# brobotESP12_2.net
KiCad netlist of a schematic drawn in EAGLE
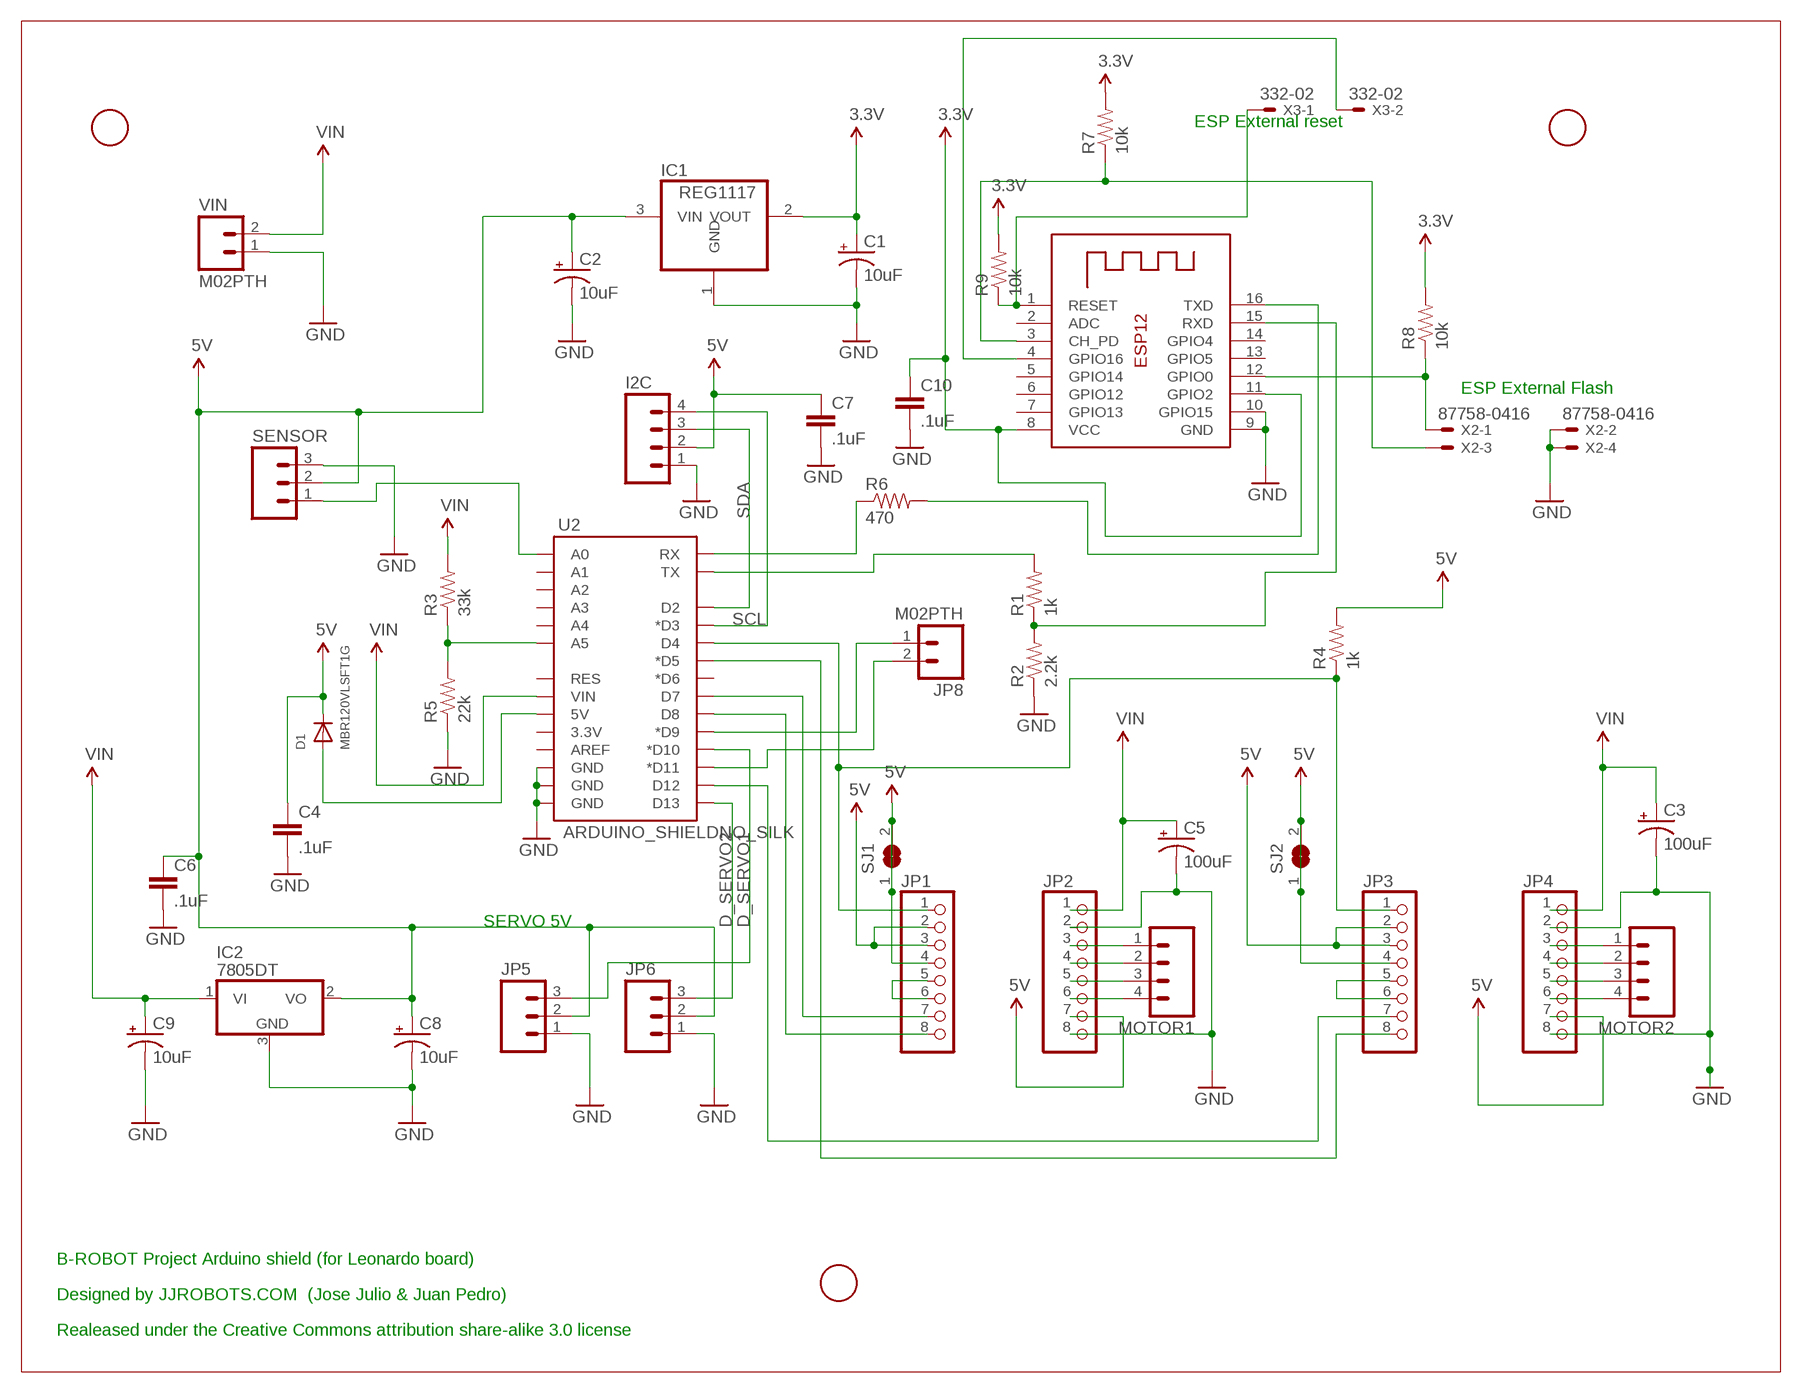
[diagram p0: schematic, sheet 1]
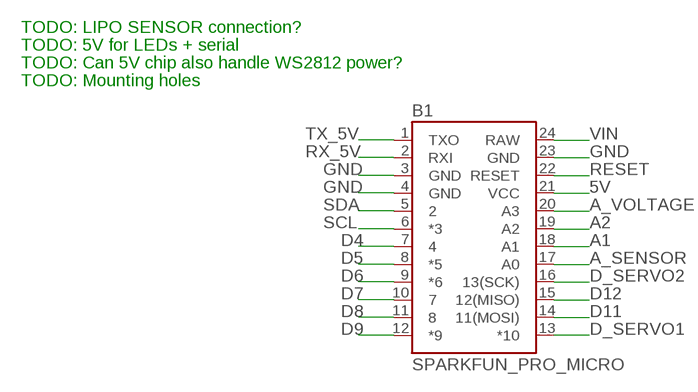
[diagram p1: schematic, sheet 2]

(export (version "E")
  (design (tool "Eeschema 10.0.6"))
  (components
    (comp (ref "B1")
      (value "SPARKFUN_PRO_MICRO")
      (footprint "eagle-import:SPARKFUN_PRO_MICRO")
      (libsource (lib "eagle-import") (part "SPARKFUN_PRO_MICRO"))
    )
    (comp (ref "C1")
      (value "10uF")
      (footprint "eagle-import:EIA3216")
      (libsource (lib "eagle-import") (part "CAP_POL1206"))
    )
    (comp (ref "C2")
      (value "10uF")
      (footprint "eagle-import:EIA3216")
      (libsource (lib "eagle-import") (part "CAP_POL1206"))
    )
    (comp (ref "C3")
      (value "100uF")
      (footprint "eagle-import:PANASONIC_D")
      (libsource (lib "eagle-import") (part "CAP_POLD"))
    )
    (comp (ref "C4")
      (value ".1uF")
      (footprint "eagle-import:0402-CAP")
      (libsource (lib "eagle-import") (part "CAP0402-CAP"))
    )
    (comp (ref "C5")
      (value "100uF")
      (footprint "eagle-import:PANASONIC_D")
      (libsource (lib "eagle-import") (part "CAP_POLD"))
    )
    (comp (ref "C6")
      (value ".1uF")
      (footprint "eagle-import:0402-CAP")
      (libsource (lib "eagle-import") (part "CAP0402-CAP"))
    )
    (comp (ref "C7")
      (value ".1uF")
      (footprint "eagle-import:0402-CAP")
      (libsource (lib "eagle-import") (part "CAP0402-CAP"))
    )
    (comp (ref "C8")
      (value "10uF")
      (footprint "eagle-import:EIA3216")
      (libsource (lib "eagle-import") (part "CAP_POL1206"))
    )
    (comp (ref "C9")
      (value "10uF")
      (footprint "eagle-import:EIA3216")
      (libsource (lib "eagle-import") (part "CAP_POL1206"))
    )
    (comp (ref "C10")
      (value ".1uF")
      (footprint "eagle-import:0402-CAP")
      (libsource (lib "eagle-import") (part "CAP0402-CAP"))
    )
    (comp (ref "D1")
      (value "MBR120VLSFT1G")
      (footprint "eagle-import:SOD-123")
      (libsource (lib "eagle-import") (part "DIODESOD-123"))
    )
    (comp (ref "I2C")
      (value "M04PTH")
      (footprint "eagle-import:1X04")
      (libsource (lib "eagle-import") (part "M04PTH"))
    )
    (comp (ref "IC1")
      (value "REG1117")
      (footprint "eagle-import:SOT223")
      (libsource (lib "eagle-import") (part "REG1117"))
    )
    (comp (ref "IC2")
      (value "7805DT")
      (footprint "eagle-import:TO252")
      (libsource (lib "eagle-import") (part "78DT05"))
    )
    (comp (ref "JP1")
      (value "PINHD-1X8")
      (footprint "eagle-import:1X08")
      (libsource (lib "eagle-import") (part "PINHD-1X8"))
    )
    (comp (ref "JP2")
      (value "PINHD-1X8")
      (footprint "eagle-import:1X08")
      (libsource (lib "eagle-import") (part "PINHD-1X8"))
    )
    (comp (ref "JP3")
      (value "PINHD-1X8")
      (footprint "eagle-import:1X08")
      (libsource (lib "eagle-import") (part "PINHD-1X8"))
    )
    (comp (ref "JP4")
      (value "PINHD-1X8")
      (footprint "eagle-import:1X08")
      (libsource (lib "eagle-import") (part "PINHD-1X8"))
    )
    (comp (ref "JP5")
      (value "M03PTH")
      (footprint "eagle-import:1X03")
      (libsource (lib "eagle-import") (part "M03PTH"))
    )
    (comp (ref "JP6")
      (value "M03PTH")
      (footprint "eagle-import:1X03")
      (libsource (lib "eagle-import") (part "M03PTH"))
    )
    (comp (ref "JP8")
      (value "M02PTH")
      (footprint "eagle-import:1X02")
      (libsource (lib "eagle-import") (part "M02PTH"))
    )
    (comp (ref "MOTOR1")
      (value "M04PTH")
      (footprint "eagle-import:1X04")
      (libsource (lib "eagle-import") (part "M04PTH"))
    )
    (comp (ref "MOTOR2")
      (value "M04PTH")
      (footprint "eagle-import:1X04")
      (libsource (lib "eagle-import") (part "M04PTH"))
    )
    (comp (ref "R1")
      (value "1k")
      (footprint "eagle-import:0805")
      (libsource (lib "eagle-import") (part "RESISTOR0805-RES"))
    )
    (comp (ref "R2")
      (value "2.2k")
      (footprint "eagle-import:0805")
      (libsource (lib "eagle-import") (part "RESISTOR0805-RES"))
    )
    (comp (ref "R3")
      (value "33k")
      (footprint "eagle-import:0805")
      (libsource (lib "eagle-import") (part "RESISTOR0805-RES"))
    )
    (comp (ref "R4")
      (value "1k")
      (footprint "eagle-import:0805")
      (libsource (lib "eagle-import") (part "RESISTOR0805-RES"))
    )
    (comp (ref "R5")
      (value "22k")
      (footprint "eagle-import:0805")
      (libsource (lib "eagle-import") (part "RESISTOR0805-RES"))
    )
    (comp (ref "R6")
      (value "470")
      (footprint "eagle-import:0805")
      (libsource (lib "eagle-import") (part "RESISTOR0805-RES"))
    )
    (comp (ref "R7")
      (value "10k")
      (footprint "eagle-import:0805")
      (libsource (lib "eagle-import") (part "RESISTOR0805-RES"))
    )
    (comp (ref "R8")
      (value "10k")
      (footprint "eagle-import:0805")
      (libsource (lib "eagle-import") (part "RESISTOR0805-RES"))
    )
    (comp (ref "R9")
      (value "10k")
      (footprint "eagle-import:0805")
      (libsource (lib "eagle-import") (part "RESISTOR0805-RES"))
    )
    (comp (ref "SENSOR")
      (value "M03PTH")
      (footprint "eagle-import:1X03")
      (libsource (lib "eagle-import") (part "M03PTH"))
    )
    (comp (ref "SJ1")
      (value "SJW")
      (footprint "eagle-import:SJW")
      (libsource (lib "eagle-import") (part "SJW"))
    )
    (comp (ref "SJ2")
      (value "SJW")
      (footprint "eagle-import:SJW")
      (libsource (lib "eagle-import") (part "SJW"))
    )
    (comp (ref "U$1")
      (value "FIDUCIAL")
      (footprint "eagle-import:FIDUCIAL_1MM")
      (libsource (lib "eagle-import") (part "FIDUCIAL"))
    )
    (comp (ref "U$2")
      (value "FIDUCIAL")
      (footprint "eagle-import:FIDUCIAL_1MM")
      (libsource (lib "eagle-import") (part "FIDUCIAL"))
    )
    (comp (ref "U$3")
      (value "FIDUCIAL")
      (footprint "eagle-import:FIDUCIAL_1MM")
      (libsource (lib "eagle-import") (part "FIDUCIAL"))
    )
    (comp (ref "U2")
      (value "ARDUINO_SHIELDNO_SILK")
      (footprint "eagle-import:DUEMILANOVE_VIAS")
      (libsource (lib "eagle-import") (part "ARDUINO_SHIELDNO_SILK"))
    )
    (comp (ref "VIN")
      (value "M02PTH")
      (footprint "eagle-import:1X02")
      (libsource (lib "eagle-import") (part "M02PTH"))
    )
    (comp (ref "X1")
      (value "ESP-12")
      (footprint "eagle-import:ESP-12")
      (libsource (lib "eagle-import") (part "ESP-12"))
    )
    (comp (ref "X2")
      (value "87758-0416")
      (footprint "eagle-import:87758-0416")
      (fields (field (name "MF") "FARNELL"))
      (libsource (lib "eagle-import") (part "87758-0416"))
    )
    (comp (ref "X3")
      (value "332-02")
      (footprint "eagle-import:332-02")
      (libsource (lib "eagle-import") (part "332-02"))
    )
  )
  (nets
    (net (code "1") (name "3.3V") (class "Default")
      (node (ref "C1") (pin "A") (pinfunction "+_A") (pintype "passive"))
      (node (ref "C10") (pin "1") (pinfunction "1_1") (pintype "passive"))
      (node (ref "IC1") (pin "2") (pinfunction "VOUT_2") (pintype "output"))
      (node (ref "R7") (pin "2") (pinfunction "2_2") (pintype "passive"))
      (node (ref "R8") (pin "2") (pinfunction "2_2") (pintype "passive"))
      (node (ref "R9") (pin "2") (pinfunction "2_2") (pintype "passive"))
      (node (ref "X1") (pin "11") (pinfunction "GPIO2_11") (pintype "bidirectional"))
      (node (ref "X1") (pin "8") (pinfunction "VCC_8") (pintype "power_in"))
    )
    (net (code "2") (name "5V") (class "Default")
      (node (ref "B1") (pin "21") (pinfunction "VCC_21") (pintype "power_in"))
      (node (ref "C2") (pin "A") (pinfunction "+_A") (pintype "passive"))
      (node (ref "C4") (pin "1") (pinfunction "1_1") (pintype "passive"))
      (node (ref "C6") (pin "1") (pinfunction "1_1") (pintype "passive"))
      (node (ref "C7") (pin "1") (pinfunction "1_1") (pintype "passive"))
      (node (ref "C8") (pin "A") (pinfunction "+_A") (pintype "passive"))
      (node (ref "D1") (pin "C") (pinfunction "C_C") (pintype "passive"))
      (node (ref "I2C") (pin "2") (pinfunction "2_2") (pintype "passive"))
      (node (ref "IC1") (pin "3") (pinfunction "VIN_3") (pintype "input"))
      (node (ref "IC2") (pin "2") (pinfunction "VO_2") (pintype "passive"))
      (node (ref "JP1") (pin "2") (pinfunction "2_2") (pintype "passive"))
      (node (ref "JP1") (pin "3") (pinfunction "3_3") (pintype "passive"))
      (node (ref "JP1") (pin "4") (pinfunction "4_4") (pintype "passive"))
      (node (ref "JP2") (pin "7") (pinfunction "7_7") (pintype "passive"))
      (node (ref "JP3") (pin "2") (pinfunction "2_2") (pintype "passive"))
      (node (ref "JP3") (pin "3") (pinfunction "3_3") (pintype "passive"))
      (node (ref "JP3") (pin "4") (pinfunction "4_4") (pintype "passive"))
      (node (ref "JP4") (pin "7") (pinfunction "7_7") (pintype "passive"))
      (node (ref "JP5") (pin "2") (pinfunction "2_2") (pintype "passive"))
      (node (ref "JP6") (pin "2") (pinfunction "2_2") (pintype "passive"))
      (node (ref "R4") (pin "2") (pinfunction "2_2") (pintype "passive"))
      (node (ref "SENSOR") (pin "2") (pinfunction "2_2") (pintype "passive"))
      (node (ref "SJ1") (pin "1") (pinfunction "1_1") (pintype "passive"))
      (node (ref "SJ1") (pin "2") (pinfunction "2_2") (pintype "passive"))
      (node (ref "SJ2") (pin "1") (pinfunction "1_1") (pintype "passive"))
      (node (ref "SJ2") (pin "2") (pinfunction "2_2") (pintype "passive"))
    )
    (net (code "3") (name "A1") (class "Default")
      (node (ref "B1") (pin "18") (pinfunction "A1_18") (pintype "bidirectional"))
    )
    (net (code "4") (name "A2") (class "Default")
      (node (ref "B1") (pin "19") (pinfunction "A2_19") (pintype "bidirectional"))
    )
    (net (code "5") (name "A_SENSOR") (class "Default")
      (node (ref "B1") (pin "17") (pinfunction "A0_17") (pintype "bidirectional"))
      (node (ref "SENSOR") (pin "1") (pinfunction "1_1") (pintype "passive"))
      (node (ref "U2") (pin "A0") (pinfunction "A0_A0") (pintype "bidirectional"))
    )
    (net (code "6") (name "A_VOLTAGE") (class "Default")
      (node (ref "B1") (pin "20") (pinfunction "A3_20") (pintype "bidirectional"))
      (node (ref "R3") (pin "1") (pinfunction "1_1") (pintype "passive"))
      (node (ref "R5") (pin "2") (pinfunction "2_2") (pintype "passive"))
      (node (ref "U2") (pin "A5") (pinfunction "A5_A5") (pintype "bidirectional"))
    )
    (net (code "7") (name "D4") (class "Default")
      (node (ref "B1") (pin "7") (pinfunction "4_7") (pintype "bidirectional"))
      (node (ref "JP1") (pin "1") (pinfunction "1_1") (pintype "passive"))
      (node (ref "JP3") (pin "1") (pinfunction "1_1") (pintype "passive"))
      (node (ref "R4") (pin "1") (pinfunction "1_1") (pintype "passive"))
      (node (ref "U2") (pin "D4") (pinfunction "D4_D4") (pintype "bidirectional"))
    )
    (net (code "8") (name "D5") (class "Default")
      (node (ref "B1") (pin "8") (pinfunction "*5_8") (pintype "bidirectional"))
      (node (ref "JP3") (pin "8") (pinfunction "8_8") (pintype "passive"))
      (node (ref "U2") (pin "D5") (pinfunction "*D5_D5") (pintype "bidirectional"))
    )
    (net (code "9") (name "D6") (class "Default")
      (node (ref "B1") (pin "9") (pinfunction "*6_9") (pintype "bidirectional"))
    )
    (net (code "10") (name "D7") (class "Default")
      (node (ref "B1") (pin "10") (pinfunction "7_10") (pintype "bidirectional"))
      (node (ref "JP1") (pin "7") (pinfunction "7_7") (pintype "passive"))
      (node (ref "U2") (pin "D7") (pinfunction "D7_D7") (pintype "bidirectional"))
    )
    (net (code "11") (name "D8") (class "Default")
      (node (ref "B1") (pin "11") (pinfunction "8_11") (pintype "bidirectional"))
      (node (ref "JP1") (pin "8") (pinfunction "8_8") (pintype "passive"))
      (node (ref "U2") (pin "D8") (pinfunction "D8_D8") (pintype "bidirectional"))
    )
    (net (code "12") (name "D9") (class "Default")
      (node (ref "B1") (pin "12") (pinfunction "*9_12") (pintype "bidirectional"))
    )
    (net (code "13") (name "D11") (class "Default")
      (node (ref "B1") (pin "14") (pinfunction "11(MOSI)_14") (pintype "bidirectional"))
      (node (ref "JP8") (pin "2") (pinfunction "2_2") (pintype "passive"))
      (node (ref "U2") (pin "D11") (pinfunction "*D11_D11") (pintype "bidirectional"))
    )
    (net (code "14") (name "D12") (class "Default")
      (node (ref "B1") (pin "15") (pinfunction "12(MISO)_15") (pintype "bidirectional"))
      (node (ref "JP3") (pin "7") (pinfunction "7_7") (pintype "passive"))
      (node (ref "U2") (pin "D12") (pinfunction "D12_D12") (pintype "bidirectional"))
    )
    (net (code "15") (name "D_SERVO1") (class "Default")
      (node (ref "B1") (pin "13") (pinfunction "*10_13") (pintype "bidirectional"))
      (node (ref "JP5") (pin "3") (pinfunction "3_3") (pintype "passive"))
      (node (ref "U2") (pin "D10") (pinfunction "*D10_D10") (pintype "bidirectional"))
    )
    (net (code "16") (name "D_SERVO2") (class "Default")
      (node (ref "B1") (pin "16") (pinfunction "13(SCK)_16") (pintype "bidirectional"))
      (node (ref "JP6") (pin "3") (pinfunction "3_3") (pintype "passive"))
      (node (ref "U2") (pin "D13") (pinfunction "D13_D13") (pintype "bidirectional"))
    )
    (net (code "17") (name "GND") (class "Default")
      (node (ref "B1") (pin "23") (pinfunction "GND_23") (pintype "power_in"))
      (node (ref "B1") (pin "3") (pinfunction "GND_3") (pintype "power_in"))
      (node (ref "B1") (pin "4") (pinfunction "GND_4") (pintype "power_in"))
      (node (ref "C1") (pin "C") (pinfunction "-_C") (pintype "passive"))
      (node (ref "C10") (pin "2") (pinfunction "2_2") (pintype "passive"))
      (node (ref "C2") (pin "C") (pinfunction "-_C") (pintype "passive"))
      (node (ref "C3") (pin "-") (pinfunction "-_-") (pintype "passive"))
      (node (ref "C4") (pin "2") (pinfunction "2_2") (pintype "passive"))
      (node (ref "C5") (pin "-") (pinfunction "-_-") (pintype "passive"))
      (node (ref "C6") (pin "2") (pinfunction "2_2") (pintype "passive"))
      (node (ref "C7") (pin "2") (pinfunction "2_2") (pintype "passive"))
      (node (ref "C8") (pin "C") (pinfunction "-_C") (pintype "passive"))
      (node (ref "C9") (pin "C") (pinfunction "-_C") (pintype "passive"))
      (node (ref "I2C") (pin "1") (pinfunction "1_1") (pintype "passive"))
      (node (ref "IC1") (pin "1") (pinfunction "GND_1") (pintype "power_in"))
      (node (ref "IC2") (pin "3") (pinfunction "GND_3") (pintype "passive"))
      (node (ref "JP2") (pin "2") (pinfunction "2_2") (pintype "passive"))
      (node (ref "JP2") (pin "8") (pinfunction "8_8") (pintype "passive"))
      (node (ref "JP4") (pin "2") (pinfunction "2_2") (pintype "passive"))
      (node (ref "JP4") (pin "8") (pinfunction "8_8") (pintype "passive"))
      (node (ref "JP5") (pin "1") (pinfunction "1_1") (pintype "passive"))
      (node (ref "JP6") (pin "1") (pinfunction "1_1") (pintype "passive"))
      (node (ref "R2") (pin "1") (pinfunction "1_1") (pintype "passive"))
      (node (ref "R5") (pin "1") (pinfunction "1_1") (pintype "passive"))
      (node (ref "SENSOR") (pin "3") (pinfunction "3_3") (pintype "passive"))
      (node (ref "U2") (pin "GND@0") (pinfunction "GND_GND@0") (pintype "bidirectional"))
      (node (ref "U2") (pin "GND@1") (pinfunction "GND_GND@1") (pintype "bidirectional"))
      (node (ref "U2") (pin "GND@2") (pinfunction "GND_GND@2") (pintype "bidirectional"))
      (node (ref "VIN") (pin "1") (pinfunction "1_1") (pintype "passive"))
      (node (ref "X1") (pin "10") (pinfunction "GPIO15_10") (pintype "bidirectional"))
      (node (ref "X1") (pin "9") (pinfunction "GND_9") (pintype "power_in"))
      (node (ref "X2") (pin "2") (pinfunction "S_2") (pintype "passive"))
      (node (ref "X2") (pin "4") (pinfunction "S_4") (pintype "passive"))
    )
    (net (code "18") (name "Net-(D1-PadA)") (class "Default")
      (node (ref "D1") (pin "A") (pinfunction "A_A") (pintype "passive"))
      (node (ref "U2") (pin "5V") (pinfunction "5V_5V") (pintype "bidirectional"))
    )
    (net (code "19") (name "Net-(JP1-Pad5)") (class "Default")
      (node (ref "JP1") (pin "5") (pinfunction "5_5") (pintype "passive"))
      (node (ref "JP1") (pin "6") (pinfunction "6_6") (pintype "passive"))
    )
    (net (code "20") (name "Net-(JP2-Pad3)") (class "Default")
      (node (ref "JP2") (pin "3") (pinfunction "3_3") (pintype "passive"))
      (node (ref "MOTOR1") (pin "1") (pinfunction "1_1") (pintype "passive"))
    )
    (net (code "21") (name "Net-(JP2-Pad4)") (class "Default")
      (node (ref "JP2") (pin "4") (pinfunction "4_4") (pintype "passive"))
      (node (ref "MOTOR1") (pin "2") (pinfunction "2_2") (pintype "passive"))
    )
    (net (code "22") (name "Net-(JP2-Pad5)") (class "Default")
      (node (ref "JP2") (pin "5") (pinfunction "5_5") (pintype "passive"))
      (node (ref "MOTOR1") (pin "3") (pinfunction "3_3") (pintype "passive"))
    )
    (net (code "23") (name "Net-(JP2-Pad6)") (class "Default")
      (node (ref "JP2") (pin "6") (pinfunction "6_6") (pintype "passive"))
      (node (ref "MOTOR1") (pin "4") (pinfunction "4_4") (pintype "passive"))
    )
    (net (code "24") (name "Net-(JP3-Pad5)") (class "Default")
      (node (ref "JP3") (pin "5") (pinfunction "5_5") (pintype "passive"))
      (node (ref "JP3") (pin "6") (pinfunction "6_6") (pintype "passive"))
    )
    (net (code "25") (name "Net-(JP4-Pad3)") (class "Default")
      (node (ref "JP4") (pin "3") (pinfunction "3_3") (pintype "passive"))
      (node (ref "MOTOR2") (pin "1") (pinfunction "1_1") (pintype "passive"))
    )
    (net (code "26") (name "Net-(JP4-Pad4)") (class "Default")
      (node (ref "JP4") (pin "4") (pinfunction "4_4") (pintype "passive"))
      (node (ref "MOTOR2") (pin "2") (pinfunction "2_2") (pintype "passive"))
    )
    (net (code "27") (name "Net-(JP4-Pad5)") (class "Default")
      (node (ref "JP4") (pin "5") (pinfunction "5_5") (pintype "passive"))
      (node (ref "MOTOR2") (pin "3") (pinfunction "3_3") (pintype "passive"))
    )
    (net (code "28") (name "Net-(JP4-Pad6)") (class "Default")
      (node (ref "JP4") (pin "6") (pinfunction "6_6") (pintype "passive"))
      (node (ref "MOTOR2") (pin "4") (pinfunction "4_4") (pintype "passive"))
    )
    (net (code "29") (name "Net-(U2-*D9)") (class "Default")
      (node (ref "JP8") (pin "1") (pinfunction "1_1") (pintype "passive"))
      (node (ref "U2") (pin "D9") (pinfunction "*D9_D9") (pintype "bidirectional"))
    )
    (net (code "30") (name "Net-(X1-CH_PD)") (class "Default")
      (node (ref "R7") (pin "1") (pinfunction "1_1") (pintype "passive"))
      (node (ref "X1") (pin "3") (pinfunction "CH_PD_3") (pintype "input"))
      (node (ref "X2") (pin "3") (pinfunction "S_3") (pintype "passive"))
    )
    (net (code "31") (name "Net-(X1-GPIO0)") (class "Default")
      (node (ref "R8") (pin "1") (pinfunction "1_1") (pintype "passive"))
      (node (ref "X1") (pin "12") (pinfunction "GPIO0_12") (pintype "bidirectional"))
      (node (ref "X2") (pin "1") (pinfunction "S_1") (pintype "passive"))
    )
    (net (code "32") (name "Net-(X1-GPIO16)") (class "Default")
      (node (ref "X1") (pin "4") (pinfunction "GPIO16_4") (pintype "bidirectional"))
      (node (ref "X3") (pin "2") (pinfunction "S_2") (pintype "passive"))
    )
    (net (code "33") (name "Net-(X1-RESET)") (class "Default")
      (node (ref "R9") (pin "1") (pinfunction "1_1") (pintype "passive"))
      (node (ref "X1") (pin "1") (pinfunction "RESET_1") (pintype "input"))
      (node (ref "X3") (pin "1") (pinfunction "S_1") (pintype "passive"))
    )
    (net (code "34") (name "Net-(X1-RXD)") (class "Default")
      (node (ref "R1") (pin "1") (pinfunction "1_1") (pintype "passive"))
      (node (ref "R2") (pin "2") (pinfunction "2_2") (pintype "passive"))
      (node (ref "X1") (pin "15") (pinfunction "RXD_15") (pintype "input"))
    )
    (net (code "35") (name "Net-(X1-TXD)") (class "Default")
      (node (ref "R6") (pin "2") (pinfunction "2_2") (pintype "passive"))
      (node (ref "X1") (pin "16") (pinfunction "TXD_16") (pintype "output"))
    )
    (net (code "36") (name "RESET") (class "Default")
      (node (ref "B1") (pin "22") (pinfunction "RESET_22") (pintype "bidirectional"))
    )
    (net (code "37") (name "RX_5V") (class "Default")
      (node (ref "B1") (pin "2") (pinfunction "RXI_2") (pintype "bidirectional"))
      (node (ref "R6") (pin "1") (pinfunction "1_1") (pintype "passive"))
      (node (ref "U2") (pin "RX") (pinfunction "RX_RX") (pintype "bidirectional"))
    )
    (net (code "38") (name "SCL") (class "Default")
      (node (ref "B1") (pin "6") (pinfunction "*3_6") (pintype "bidirectional"))
      (node (ref "I2C") (pin "4") (pinfunction "4_4") (pintype "passive"))
      (node (ref "U2") (pin "D3") (pinfunction "*D3_D3") (pintype "bidirectional"))
    )
    (net (code "39") (name "SDA") (class "Default")
      (node (ref "B1") (pin "5") (pinfunction "2_5") (pintype "bidirectional"))
      (node (ref "I2C") (pin "3") (pinfunction "3_3") (pintype "passive"))
      (node (ref "U2") (pin "D2") (pinfunction "D2_D2") (pintype "bidirectional"))
    )
    (net (code "40") (name "TX_5V") (class "Default")
      (node (ref "B1") (pin "1") (pinfunction "TXO_1") (pintype "bidirectional"))
      (node (ref "R1") (pin "2") (pinfunction "2_2") (pintype "passive"))
      (node (ref "U2") (pin "TX") (pinfunction "TX_TX") (pintype "bidirectional"))
    )
    (net (code "41") (name "VIN") (class "Default")
      (node (ref "B1") (pin "24") (pinfunction "RAW_24") (pintype "power_in"))
      (node (ref "C3") (pin "+") (pinfunction "+_+") (pintype "passive"))
      (node (ref "C5") (pin "+") (pinfunction "+_+") (pintype "passive"))
      (node (ref "C9") (pin "A") (pinfunction "+_A") (pintype "passive"))
      (node (ref "IC2") (pin "1") (pinfunction "VI_1") (pintype "input"))
      (node (ref "JP2") (pin "1") (pinfunction "1_1") (pintype "passive"))
      (node (ref "JP4") (pin "1") (pinfunction "1_1") (pintype "passive"))
      (node (ref "R3") (pin "2") (pinfunction "2_2") (pintype "passive"))
      (node (ref "U2") (pin "VIN") (pinfunction "VIN_VIN") (pintype "bidirectional"))
      (node (ref "VIN") (pin "2") (pinfunction "2_2") (pintype "passive"))
    )
    (net (code "42") (name "unconnected-(U2-*D6-PadD6)") (class "Default")
      (node (ref "U2") (pin "D6") (pinfunction "*D6_D6") (pintype "bidirectional"))
    )
    (net (code "43") (name "unconnected-(U2-Pad3.3V)") (class "Default")
      (node (ref "U2") (pin "3.3V") (pinfunction "3.3V_3.3V") (pintype "bidirectional"))
    )
    (net (code "44") (name "unconnected-(U2-PadA1)") (class "Default")
      (node (ref "U2") (pin "A1") (pinfunction "A1_A1") (pintype "bidirectional"))
    )
    (net (code "45") (name "unconnected-(U2-PadA2)") (class "Default")
      (node (ref "U2") (pin "A2") (pinfunction "A2_A2") (pintype "bidirectional"))
    )
    (net (code "46") (name "unconnected-(U2-PadA3)") (class "Default")
      (node (ref "U2") (pin "A3") (pinfunction "A3_A3") (pintype "bidirectional"))
    )
    (net (code "47") (name "unconnected-(U2-PadA4)") (class "Default")
      (node (ref "U2") (pin "A4") (pinfunction "A4_A4") (pintype "bidirectional"))
    )
    (net (code "48") (name "unconnected-(U2-PadAREF)") (class "Default")
      (node (ref "U2") (pin "AREF") (pinfunction "AREF_AREF") (pintype "bidirectional"))
    )
    (net (code "49") (name "unconnected-(U2-PadRES)") (class "Default")
      (node (ref "U2") (pin "RES") (pinfunction "RES_RES") (pintype "bidirectional"))
    )
    (net (code "50") (name "unconnected-(X1-ADC-Pad2)") (class "Default")
      (node (ref "X1") (pin "2") (pinfunction "ADC_2") (pintype "passive"))
    )
    (net (code "51") (name "unconnected-(X1-GPIO4-Pad14)") (class "Default")
      (node (ref "X1") (pin "14") (pinfunction "GPIO4_14") (pintype "bidirectional"))
    )
    (net (code "52") (name "unconnected-(X1-GPIO5-Pad13)") (class "Default")
      (node (ref "X1") (pin "13") (pinfunction "GPIO5_13") (pintype "bidirectional"))
    )
    (net (code "53") (name "unconnected-(X1-GPIO12-Pad6)") (class "Default")
      (node (ref "X1") (pin "6") (pinfunction "GPIO12_6") (pintype "bidirectional"))
    )
    (net (code "54") (name "unconnected-(X1-GPIO13-Pad7)") (class "Default")
      (node (ref "X1") (pin "7") (pinfunction "GPIO13_7") (pintype "bidirectional"))
    )
    (net (code "55") (name "unconnected-(X1-GPIO14-Pad5)") (class "Default")
      (node (ref "X1") (pin "5") (pinfunction "GPIO14_5") (pintype "bidirectional"))
    )
  )
)
